# Wireless_Weather_Station.net
KiCad netlist of a schematic drawn in EAGLE
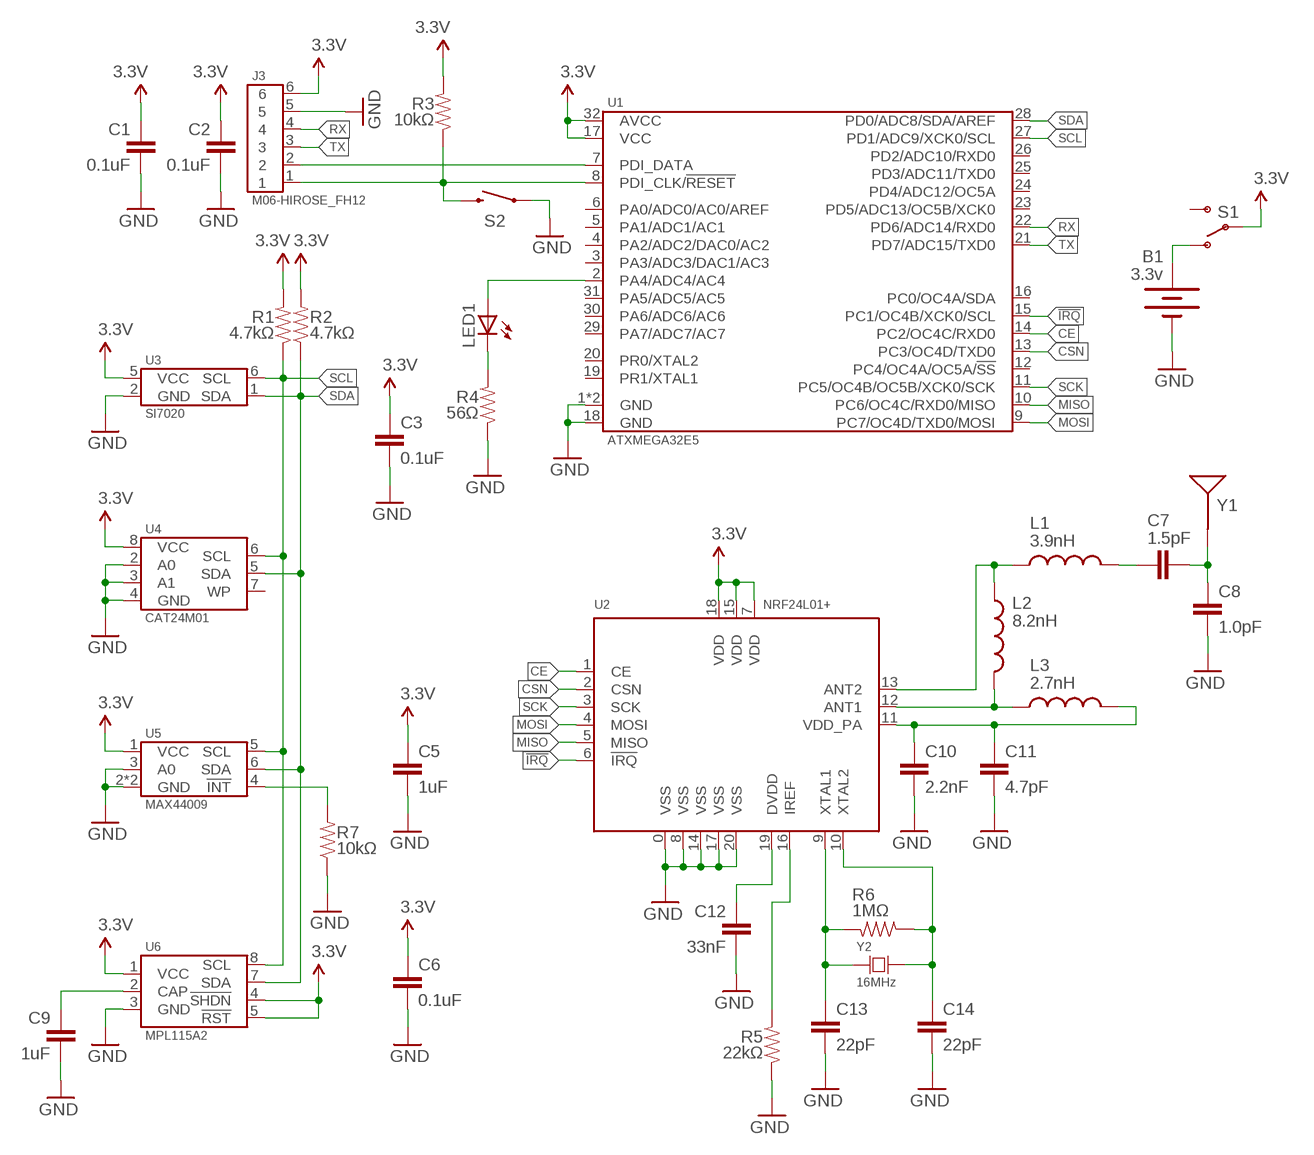
[diagram p0: schematic, sheet 1]

(export (version "E")
  (design (tool "Eeschema 10.0.6"))
  (components
    (comp (ref "B1")
      (value "3.3v")
      (footprint "eagle-import:BATTCON_20MM_SEWABLE")
      (libsource (lib "eagle-import") (part "BATTERY20MM-SEWABLE"))
    )
    (comp (ref "C1")
      (value "0.1uF")
      (footprint "eagle-import:0402-CAP")
      (libsource (lib "eagle-import") (part "CAP0402-CAP"))
    )
    (comp (ref "C2")
      (value "0.1uF")
      (footprint "eagle-import:0402-CAP")
      (libsource (lib "eagle-import") (part "CAP0402-CAP"))
    )
    (comp (ref "C3")
      (value "0.1uF")
      (footprint "eagle-import:0402-CAP")
      (libsource (lib "eagle-import") (part "CAP0402-CAP"))
    )
    (comp (ref "C5")
      (value "1uF")
      (footprint "eagle-import:0402-CAP")
      (libsource (lib "eagle-import") (part "CAP0402-CAP"))
    )
    (comp (ref "C6")
      (value "0.1uF")
      (footprint "eagle-import:0402-CAP")
      (libsource (lib "eagle-import") (part "CAP0402-CAP"))
    )
    (comp (ref "C7")
      (value "1.5pF")
      (footprint "eagle-import:0402-CAP")
      (libsource (lib "eagle-import") (part "CAP0402-CAP"))
    )
    (comp (ref "C8")
      (value "1.0pF")
      (footprint "eagle-import:0402-CAP")
      (libsource (lib "eagle-import") (part "CAP0402-CAP"))
    )
    (comp (ref "C9")
      (value "1uF")
      (footprint "eagle-import:0402-CAP")
      (libsource (lib "eagle-import") (part "CAP0402-CAP"))
    )
    (comp (ref "C10")
      (value "2.2nF")
      (footprint "eagle-import:0402-CAP")
      (libsource (lib "eagle-import") (part "CAP0402-CAP"))
    )
    (comp (ref "C11")
      (value "4.7pF")
      (footprint "eagle-import:0402-CAP")
      (libsource (lib "eagle-import") (part "CAP0402-CAP"))
    )
    (comp (ref "C12")
      (value "33nF")
      (footprint "eagle-import:0402-CAP")
      (libsource (lib "eagle-import") (part "CAP0402-CAP"))
    )
    (comp (ref "C13")
      (value "22pF")
      (footprint "eagle-import:0402-CAP")
      (libsource (lib "eagle-import") (part "CAP0402-CAP"))
    )
    (comp (ref "C14")
      (value "22pF")
      (footprint "eagle-import:0402-CAP")
      (libsource (lib "eagle-import") (part "CAP0402-CAP"))
    )
    (comp (ref "J3")
      (value "M06-HIROSE_FH12")
      (footprint "eagle-import:FH12-6S-1SH(55)")
      (libsource (lib "eagle-import") (part "M06-HIROSE_FH12"))
    )
    (comp (ref "L1")
      (value "3.9nH")
      (footprint "eagle-import:C0402")
      (libsource (lib "eagle-import") (part "INDUCTOR0402"))
    )
    (comp (ref "L2")
      (value "8.2nH")
      (footprint "eagle-import:C0402")
      (libsource (lib "eagle-import") (part "INDUCTOR0402"))
    )
    (comp (ref "L3")
      (value "2.7nH")
      (footprint "eagle-import:C0402")
      (libsource (lib "eagle-import") (part "INDUCTOR0402"))
    )
    (comp (ref "LED1")
      (value "LED0603")
      (footprint "eagle-import:LED-0603")
      (libsource (lib "eagle-import") (part "LED0603"))
    )
    (comp (ref "R1")
      (value "4.7kΩ")
      (footprint "eagle-import:0402-RES")
      (libsource (lib "eagle-import") (part "RESISTOR0402-RES"))
    )
    (comp (ref "R2")
      (value "4.7kΩ")
      (footprint "eagle-import:0402-RES")
      (libsource (lib "eagle-import") (part "RESISTOR0402-RES"))
    )
    (comp (ref "R3")
      (value "10kΩ")
      (footprint "eagle-import:0402-RES")
      (libsource (lib "eagle-import") (part "RESISTOR0402-RES"))
    )
    (comp (ref "R4")
      (value "56Ω")
      (footprint "eagle-import:0402-RES")
      (libsource (lib "eagle-import") (part "RESISTOR0402-RES"))
    )
    (comp (ref "R5")
      (value "22kΩ")
      (footprint "eagle-import:0402-RES")
      (libsource (lib "eagle-import") (part "RESISTOR0402-RES"))
    )
    (comp (ref "R6")
      (value "1MΩ")
      (footprint "eagle-import:0402-RES")
      (libsource (lib "eagle-import") (part "RESISTOR0402-RES"))
    )
    (comp (ref "R7")
      (value "10kΩ")
      (footprint "eagle-import:0402-RES")
      (libsource (lib "eagle-import") (part "RESISTOR0402-RES"))
    )
    (comp (ref "S1")
      (value "SWITCH-SPDT-SMD-A")
      (footprint "eagle-import:SWITCH-SPST-SMD-A")
      (libsource (lib "eagle-import") (part "SWITCH-SPDT-SMD-A"))
    )
    (comp (ref "S2")
      (value "SWITCH-MOMENTARY-2-SMD-1101NE")
      (footprint "eagle-import:TACTILE-SWITCH-1101NE")
      (libsource (lib "eagle-import") (part "SWITCH-MOMENTARY-2-SMD-1101NE"))
    )
    (comp (ref "U1")
      (value "ATXMEGA32E5")
      (footprint "eagle-import:QFN-32")
      (libsource (lib "eagle-import") (part "ATXMEGA32E5"))
    )
    (comp (ref "U2")
      (value "NRF24L01+")
      (footprint "eagle-import:QFN-20")
      (libsource (lib "eagle-import") (part "NRF24L01+"))
    )
    (comp (ref "U3")
      (value "SI7020")
      (footprint "eagle-import:SI7020")
      (libsource (lib "eagle-import") (part "SI7020"))
    )
    (comp (ref "U4")
      (value "CAT24M01")
      (footprint "eagle-import:SO-8")
      (libsource (lib "eagle-import") (part "CAT24M01"))
    )
    (comp (ref "U5")
      (value "MAX44009")
      (footprint "eagle-import:MAX44009")
      (libsource (lib "eagle-import") (part "MAX44009"))
    )
    (comp (ref "U6")
      (value "MPL115A2")
      (footprint "eagle-import:MPL115A1")
      (libsource (lib "eagle-import") (part "MPL115A2"))
    )
    (comp (ref "Y1")
      (value "ANTENNA2SMD5")
      (footprint "eagle-import:ANTENNA-CHIP5")
      (libsource (lib "eagle-import") (part "ANTENNA2SMD5"))
    )
    (comp (ref "Y2")
      (value "16MHz")
      (footprint "eagle-import:FA-238")
      (libsource (lib "eagle-import") (part "CRYSTAL-3.2X2.5"))
    )
  )
  (nets
    (net (code "1") (name "/~{IRQ}") (class "Default")
      (node (ref "U1") (pin "15") (pinfunction "PC1/OC4B/XCK0/SCL_15") (pintype "bidirectional"))
      (node (ref "U2") (pin "6") (pinfunction "~{IRQ}_6") (pintype "bidirectional"))
    )
    (net (code "2") (name "3.3V") (class "Default")
      (node (ref "C1") (pin "1") (pinfunction "1_1") (pintype "passive"))
      (node (ref "C2") (pin "1") (pinfunction "1_1") (pintype "passive"))
      (node (ref "C3") (pin "1") (pinfunction "1_1") (pintype "passive"))
      (node (ref "C5") (pin "1") (pinfunction "1_1") (pintype "passive"))
      (node (ref "C6") (pin "1") (pinfunction "1_1") (pintype "passive"))
      (node (ref "J3") (pin "6") (pinfunction "6_6") (pintype "bidirectional"))
      (node (ref "R1") (pin "2") (pinfunction "2_2") (pintype "passive"))
      (node (ref "R2") (pin "2") (pinfunction "2_2") (pintype "passive"))
      (node (ref "R3") (pin "2") (pinfunction "2_2") (pintype "passive"))
      (node (ref "S1") (pin "2") (pinfunction "P_2") (pintype "passive"))
      (node (ref "U1") (pin "17") (pinfunction "VCC_17") (pintype "bidirectional"))
      (node (ref "U1") (pin "32") (pinfunction "AVCC_32") (pintype "bidirectional"))
      (node (ref "U2") (pin "15") (pinfunction "VDD_15") (pintype "bidirectional"))
      (node (ref "U2") (pin "18") (pinfunction "VDD_18") (pintype "bidirectional"))
      (node (ref "U2") (pin "7") (pinfunction "VDD_7") (pintype "bidirectional"))
      (node (ref "U3") (pin "5") (pinfunction "VCC_5") (pintype "bidirectional"))
      (node (ref "U4") (pin "8") (pinfunction "VCC_8") (pintype "bidirectional"))
      (node (ref "U5") (pin "1") (pinfunction "VCC_1") (pintype "bidirectional"))
      (node (ref "U6") (pin "1") (pinfunction "VCC_1") (pintype "bidirectional"))
      (node (ref "U6") (pin "4") (pinfunction "~{SHDN}_4") (pintype "bidirectional"))
      (node (ref "U6") (pin "5") (pinfunction "~{RST}_5") (pintype "bidirectional"))
    )
    (net (code "3") (name "CE") (class "Default")
      (node (ref "U1") (pin "14") (pinfunction "PC2/OC4C/RXD0_14") (pintype "bidirectional"))
      (node (ref "U2") (pin "1") (pinfunction "CE_1") (pintype "bidirectional"))
    )
    (net (code "4") (name "CSN") (class "Default")
      (node (ref "U1") (pin "13") (pinfunction "PC3/OC4D/TXD0_13") (pintype "bidirectional"))
      (node (ref "U2") (pin "2") (pinfunction "CSN_2") (pintype "bidirectional"))
    )
    (net (code "5") (name "GND") (class "Default")
      (node (ref "B1") (pin "2") (pinfunction "-_2") (pintype "power_in"))
      (node (ref "C1") (pin "2") (pinfunction "2_2") (pintype "passive"))
      (node (ref "C10") (pin "2") (pinfunction "2_2") (pintype "passive"))
      (node (ref "C11") (pin "2") (pinfunction "2_2") (pintype "passive"))
      (node (ref "C12") (pin "2") (pinfunction "2_2") (pintype "passive"))
      (node (ref "C13") (pin "2") (pinfunction "2_2") (pintype "passive"))
      (node (ref "C14") (pin "2") (pinfunction "2_2") (pintype "passive"))
      (node (ref "C2") (pin "2") (pinfunction "2_2") (pintype "passive"))
      (node (ref "C3") (pin "2") (pinfunction "2_2") (pintype "passive"))
      (node (ref "C5") (pin "2") (pinfunction "2_2") (pintype "passive"))
      (node (ref "C6") (pin "2") (pinfunction "2_2") (pintype "passive"))
      (node (ref "C8") (pin "2") (pinfunction "2_2") (pintype "passive"))
      (node (ref "C9") (pin "2") (pinfunction "2_2") (pintype "passive"))
      (node (ref "J3") (pin "5") (pinfunction "5_5") (pintype "bidirectional"))
      (node (ref "R4") (pin "1") (pinfunction "1_1") (pintype "passive"))
      (node (ref "R5") (pin "1") (pinfunction "1_1") (pintype "passive"))
      (node (ref "R7") (pin "1") (pinfunction "1_1") (pintype "passive"))
      (node (ref "S2") (pin "P$1") (pinfunction "1_P$1") (pintype "passive"))
      (node (ref "U1") (pin "1") (pinfunction "GND_1") (pintype "bidirectional"))
      (node (ref "U1") (pin "18") (pinfunction "GND_18") (pintype "bidirectional"))
      (node (ref "U1") (pin "EP") (pinfunction "GND_EP") (pintype "bidirectional"))
      (node (ref "U2") (pin "0") (pinfunction "VSS_0") (pintype "bidirectional"))
      (node (ref "U2") (pin "14") (pinfunction "VSS_14") (pintype "bidirectional"))
      (node (ref "U2") (pin "17") (pinfunction "VSS_17") (pintype "bidirectional"))
      (node (ref "U2") (pin "20") (pinfunction "VSS_20") (pintype "bidirectional"))
      (node (ref "U2") (pin "8") (pinfunction "VSS_8") (pintype "bidirectional"))
      (node (ref "U3") (pin "2") (pinfunction "GND_2") (pintype "bidirectional"))
      (node (ref "U4") (pin "2") (pinfunction "A0_2") (pintype "bidirectional"))
      (node (ref "U4") (pin "3") (pinfunction "A1_3") (pintype "bidirectional"))
      (node (ref "U4") (pin "4") (pinfunction "GND_4") (pintype "bidirectional"))
      (node (ref "U5") (pin "2") (pinfunction "GND_2") (pintype "bidirectional"))
      (node (ref "U5") (pin "3") (pinfunction "A0_3") (pintype "bidirectional"))
      (node (ref "U5") (pin "PAD") (pinfunction "GND_PAD") (pintype "bidirectional"))
      (node (ref "U6") (pin "3") (pinfunction "GND_3") (pintype "bidirectional"))
    )
    (net (code "6") (name "MISO") (class "Default")
      (node (ref "U1") (pin "10") (pinfunction "PC6/OC4C/RXD0/MISO_10") (pintype "bidirectional"))
      (node (ref "U2") (pin "5") (pinfunction "MISO_5") (pintype "bidirectional"))
    )
    (net (code "7") (name "MOSI") (class "Default")
      (node (ref "U1") (pin "9") (pinfunction "PC7/OC4D/TXD0/MOSI_9") (pintype "bidirectional"))
      (node (ref "U2") (pin "4") (pinfunction "MOSI_4") (pintype "bidirectional"))
    )
    (net (code "8") (name "Net-(B1-+)") (class "Default")
      (node (ref "B1") (pin "1") (pinfunction "+_1") (pintype "power_in"))
      (node (ref "S1") (pin "1") (pinfunction "O_1") (pintype "passive"))
    )
    (net (code "9") (name "Net-(C7-Pad1)") (class "Default")
      (node (ref "C7") (pin "1") (pinfunction "1_1") (pintype "passive"))
      (node (ref "L1") (pin "2") (pinfunction "2_2") (pintype "passive"))
    )
    (net (code "10") (name "Net-(LED1-PadC)") (class "Default")
      (node (ref "LED1") (pin "C") (pinfunction "C_C") (pintype "passive"))
      (node (ref "R4") (pin "2") (pinfunction "2_2") (pintype "passive"))
    )
    (net (code "11") (name "Net-(S2-2)") (class "Default")
      (node (ref "J3") (pin "1") (pinfunction "1_1") (pintype "bidirectional"))
      (node (ref "R3") (pin "1") (pinfunction "1_1") (pintype "passive"))
      (node (ref "S2") (pin "P$2") (pinfunction "2_P$2") (pintype "passive"))
      (node (ref "U1") (pin "8") (pinfunction "PDI_CLK/~{RESET}_8") (pintype "bidirectional"))
    )
    (net (code "12") (name "Net-(U1-PA4{slash}ADC4{slash}AC4)") (class "Default")
      (node (ref "LED1") (pin "A") (pinfunction "A_A") (pintype "passive"))
      (node (ref "U1") (pin "2") (pinfunction "PA4/ADC4/AC4_2") (pintype "bidirectional"))
    )
    (net (code "13") (name "Net-(U1-PDI_DATA)") (class "Default")
      (node (ref "J3") (pin "2") (pinfunction "2_2") (pintype "bidirectional"))
      (node (ref "U1") (pin "7") (pinfunction "PDI_DATA_7") (pintype "bidirectional"))
    )
    (net (code "14") (name "Net-(U2-ANT1)") (class "Default")
      (node (ref "L2") (pin "2") (pinfunction "2_2") (pintype "passive"))
      (node (ref "L3") (pin "1") (pinfunction "1_1") (pintype "passive"))
      (node (ref "U2") (pin "12") (pinfunction "ANT1_12") (pintype "bidirectional"))
    )
    (net (code "15") (name "Net-(U2-ANT2)") (class "Default")
      (node (ref "L1") (pin "1") (pinfunction "1_1") (pintype "passive"))
      (node (ref "L2") (pin "1") (pinfunction "1_1") (pintype "passive"))
      (node (ref "U2") (pin "13") (pinfunction "ANT2_13") (pintype "bidirectional"))
    )
    (net (code "16") (name "Net-(U2-DVDD)") (class "Default")
      (node (ref "C12") (pin "1") (pinfunction "1_1") (pintype "passive"))
      (node (ref "U2") (pin "19") (pinfunction "DVDD_19") (pintype "bidirectional"))
    )
    (net (code "17") (name "Net-(U2-IREF)") (class "Default")
      (node (ref "R5") (pin "2") (pinfunction "2_2") (pintype "passive"))
      (node (ref "U2") (pin "16") (pinfunction "IREF_16") (pintype "bidirectional"))
    )
    (net (code "18") (name "Net-(U2-VDD_PA)") (class "Default")
      (node (ref "C10") (pin "1") (pinfunction "1_1") (pintype "passive"))
      (node (ref "C11") (pin "1") (pinfunction "1_1") (pintype "passive"))
      (node (ref "L3") (pin "2") (pinfunction "2_2") (pintype "passive"))
      (node (ref "U2") (pin "11") (pinfunction "VDD_PA_11") (pintype "bidirectional"))
    )
    (net (code "19") (name "Net-(U2-XTAL1)") (class "Default")
      (node (ref "C13") (pin "1") (pinfunction "1_1") (pintype "passive"))
      (node (ref "R6") (pin "2") (pinfunction "2_2") (pintype "passive"))
      (node (ref "U2") (pin "9") (pinfunction "XTAL1_9") (pintype "bidirectional"))
      (node (ref "Y2") (pin "1") (pinfunction "1_1") (pintype "bidirectional"))
    )
    (net (code "20") (name "Net-(U2-XTAL2)") (class "Default")
      (node (ref "C14") (pin "1") (pinfunction "1_1") (pintype "passive"))
      (node (ref "R6") (pin "1") (pinfunction "1_1") (pintype "passive"))
      (node (ref "U2") (pin "10") (pinfunction "XTAL2_10") (pintype "bidirectional"))
      (node (ref "Y2") (pin "3") (pinfunction "2_3") (pintype "bidirectional"))
    )
    (net (code "21") (name "Net-(U5-~{INT})") (class "Default")
      (node (ref "R7") (pin "2") (pinfunction "2_2") (pintype "passive"))
      (node (ref "U5") (pin "4") (pinfunction "~{INT}_4") (pintype "bidirectional"))
    )
    (net (code "22") (name "Net-(U6-CAP)") (class "Default")
      (node (ref "C9") (pin "1") (pinfunction "1_1") (pintype "passive"))
      (node (ref "U6") (pin "2") (pinfunction "CAP_2") (pintype "bidirectional"))
    )
    (net (code "23") (name "Net-(Y1-SIGNAL)") (class "Default")
      (node (ref "C7") (pin "2") (pinfunction "2_2") (pintype "passive"))
      (node (ref "C8") (pin "1") (pinfunction "1_1") (pintype "passive"))
      (node (ref "Y1") (pin "FEED") (pinfunction "SIGNAL_FEED") (pintype "bidirectional"))
    )
    (net (code "24") (name "RX") (class "Default")
      (node (ref "J3") (pin "4") (pinfunction "4_4") (pintype "bidirectional"))
      (node (ref "U1") (pin "22") (pinfunction "PD6/ADC14/RXD0_22") (pintype "bidirectional"))
    )
    (net (code "25") (name "SCK") (class "Default")
      (node (ref "U1") (pin "11") (pinfunction "PC5/OC4B/OC5B/XCK0/SCK_11") (pintype "bidirectional"))
      (node (ref "U2") (pin "3") (pinfunction "SCK_3") (pintype "bidirectional"))
    )
    (net (code "26") (name "SCL") (class "Default")
      (node (ref "R1") (pin "1") (pinfunction "1_1") (pintype "passive"))
      (node (ref "U1") (pin "27") (pinfunction "PD1/ADC9/XCK0/SCL_27") (pintype "bidirectional"))
      (node (ref "U3") (pin "6") (pinfunction "SCL_6") (pintype "bidirectional"))
      (node (ref "U4") (pin "6") (pinfunction "SCL_6") (pintype "bidirectional"))
      (node (ref "U5") (pin "5") (pinfunction "SCL_5") (pintype "bidirectional"))
      (node (ref "U6") (pin "8") (pinfunction "SCL_8") (pintype "bidirectional"))
    )
    (net (code "27") (name "SDA") (class "Default")
      (node (ref "R2") (pin "1") (pinfunction "1_1") (pintype "passive"))
      (node (ref "U1") (pin "28") (pinfunction "PD0/ADC8/SDA/AREF_28") (pintype "bidirectional"))
      (node (ref "U3") (pin "1") (pinfunction "SDA_1") (pintype "bidirectional"))
      (node (ref "U4") (pin "5") (pinfunction "SDA_5") (pintype "bidirectional"))
      (node (ref "U5") (pin "6") (pinfunction "SDA_6") (pintype "bidirectional"))
      (node (ref "U6") (pin "7") (pinfunction "SDA_7") (pintype "bidirectional"))
    )
    (net (code "28") (name "TX") (class "Default")
      (node (ref "J3") (pin "3") (pinfunction "3_3") (pintype "bidirectional"))
      (node (ref "U1") (pin "21") (pinfunction "PD7/ADC15/TXD0_21") (pintype "bidirectional"))
    )
    (net (code "29") (name "unconnected-(S1-S-Pad3)") (class "Default")
      (node (ref "S1") (pin "3") (pinfunction "S_3") (pintype "passive"))
    )
    (net (code "30") (name "unconnected-(U1-PA0{slash}ADC0{slash}AC0{slash}AREF-Pad6)") (class "Default")
      (node (ref "U1") (pin "6") (pinfunction "PA0/ADC0/AC0/AREF_6") (pintype "bidirectional"))
    )
    (net (code "31") (name "unconnected-(U1-PA1{slash}ADC1{slash}AC1-Pad5)") (class "Default")
      (node (ref "U1") (pin "5") (pinfunction "PA1/ADC1/AC1_5") (pintype "bidirectional"))
    )
    (net (code "32") (name "unconnected-(U1-PA2{slash}ADC2{slash}DAC0{slash}AC2-Pad4)") (class "Default")
      (node (ref "U1") (pin "4") (pinfunction "PA2/ADC2/DAC0/AC2_4") (pintype "bidirectional"))
    )
    (net (code "33") (name "unconnected-(U1-PA3{slash}ADC3{slash}DAC1{slash}AC3-Pad3)") (class "Default")
      (node (ref "U1") (pin "3") (pinfunction "PA3/ADC3/DAC1/AC3_3") (pintype "bidirectional"))
    )
    (net (code "34") (name "unconnected-(U1-PA5{slash}ADC5{slash}AC5-Pad31)") (class "Default")
      (node (ref "U1") (pin "31") (pinfunction "PA5/ADC5/AC5_31") (pintype "bidirectional"))
    )
    (net (code "35") (name "unconnected-(U1-PA6{slash}ADC6{slash}AC6-Pad30)") (class "Default")
      (node (ref "U1") (pin "30") (pinfunction "PA6/ADC6/AC6_30") (pintype "bidirectional"))
    )
    (net (code "36") (name "unconnected-(U1-PA7{slash}ADC7{slash}AC7-Pad29)") (class "Default")
      (node (ref "U1") (pin "29") (pinfunction "PA7/ADC7/AC7_29") (pintype "bidirectional"))
    )
    (net (code "37") (name "unconnected-(U1-PC0{slash}OC4A{slash}SDA-Pad16)") (class "Default")
      (node (ref "U1") (pin "16") (pinfunction "PC0/OC4A/SDA_16") (pintype "bidirectional"))
    )
    (net (code "38") (name "unconnected-(U1-PC4{slash}OC4A{slash}OC5A{slash}~{SS}-Pad12)") (class "Default")
      (node (ref "U1") (pin "12") (pinfunction "PC4/OC4A/OC5A/~{SS}_12") (pintype "bidirectional"))
    )
    (net (code "39") (name "unconnected-(U1-PD2{slash}ADC10{slash}RXD0-Pad26)") (class "Default")
      (node (ref "U1") (pin "26") (pinfunction "PD2/ADC10/RXD0_26") (pintype "bidirectional"))
    )
    (net (code "40") (name "unconnected-(U1-PD3{slash}ADC11{slash}TXD0-Pad25)") (class "Default")
      (node (ref "U1") (pin "25") (pinfunction "PD3/ADC11/TXD0_25") (pintype "bidirectional"))
    )
    (net (code "41") (name "unconnected-(U1-PD4{slash}ADC12{slash}OC5A-Pad24)") (class "Default")
      (node (ref "U1") (pin "24") (pinfunction "PD4/ADC12/OC5A_24") (pintype "bidirectional"))
    )
    (net (code "42") (name "unconnected-(U1-PD5{slash}ADC13{slash}OC5B{slash}XCK0-Pad23)") (class "Default")
      (node (ref "U1") (pin "23") (pinfunction "PD5/ADC13/OC5B/XCK0_23") (pintype "bidirectional"))
    )
    (net (code "43") (name "unconnected-(U1-PR0{slash}XTAL2-Pad20)") (class "Default")
      (node (ref "U1") (pin "20") (pinfunction "PR0/XTAL2_20") (pintype "bidirectional"))
    )
    (net (code "44") (name "unconnected-(U1-PR1{slash}XTAL1-Pad19)") (class "Default")
      (node (ref "U1") (pin "19") (pinfunction "PR1/XTAL1_19") (pintype "bidirectional"))
    )
    (net (code "45") (name "unconnected-(U4-WP-Pad7)") (class "Default")
      (node (ref "U4") (pin "7") (pinfunction "WP_7") (pintype "bidirectional"))
    )
  )
)
